# SCHE.net
KiCad netlist of a schematic drawn in Altium Designer
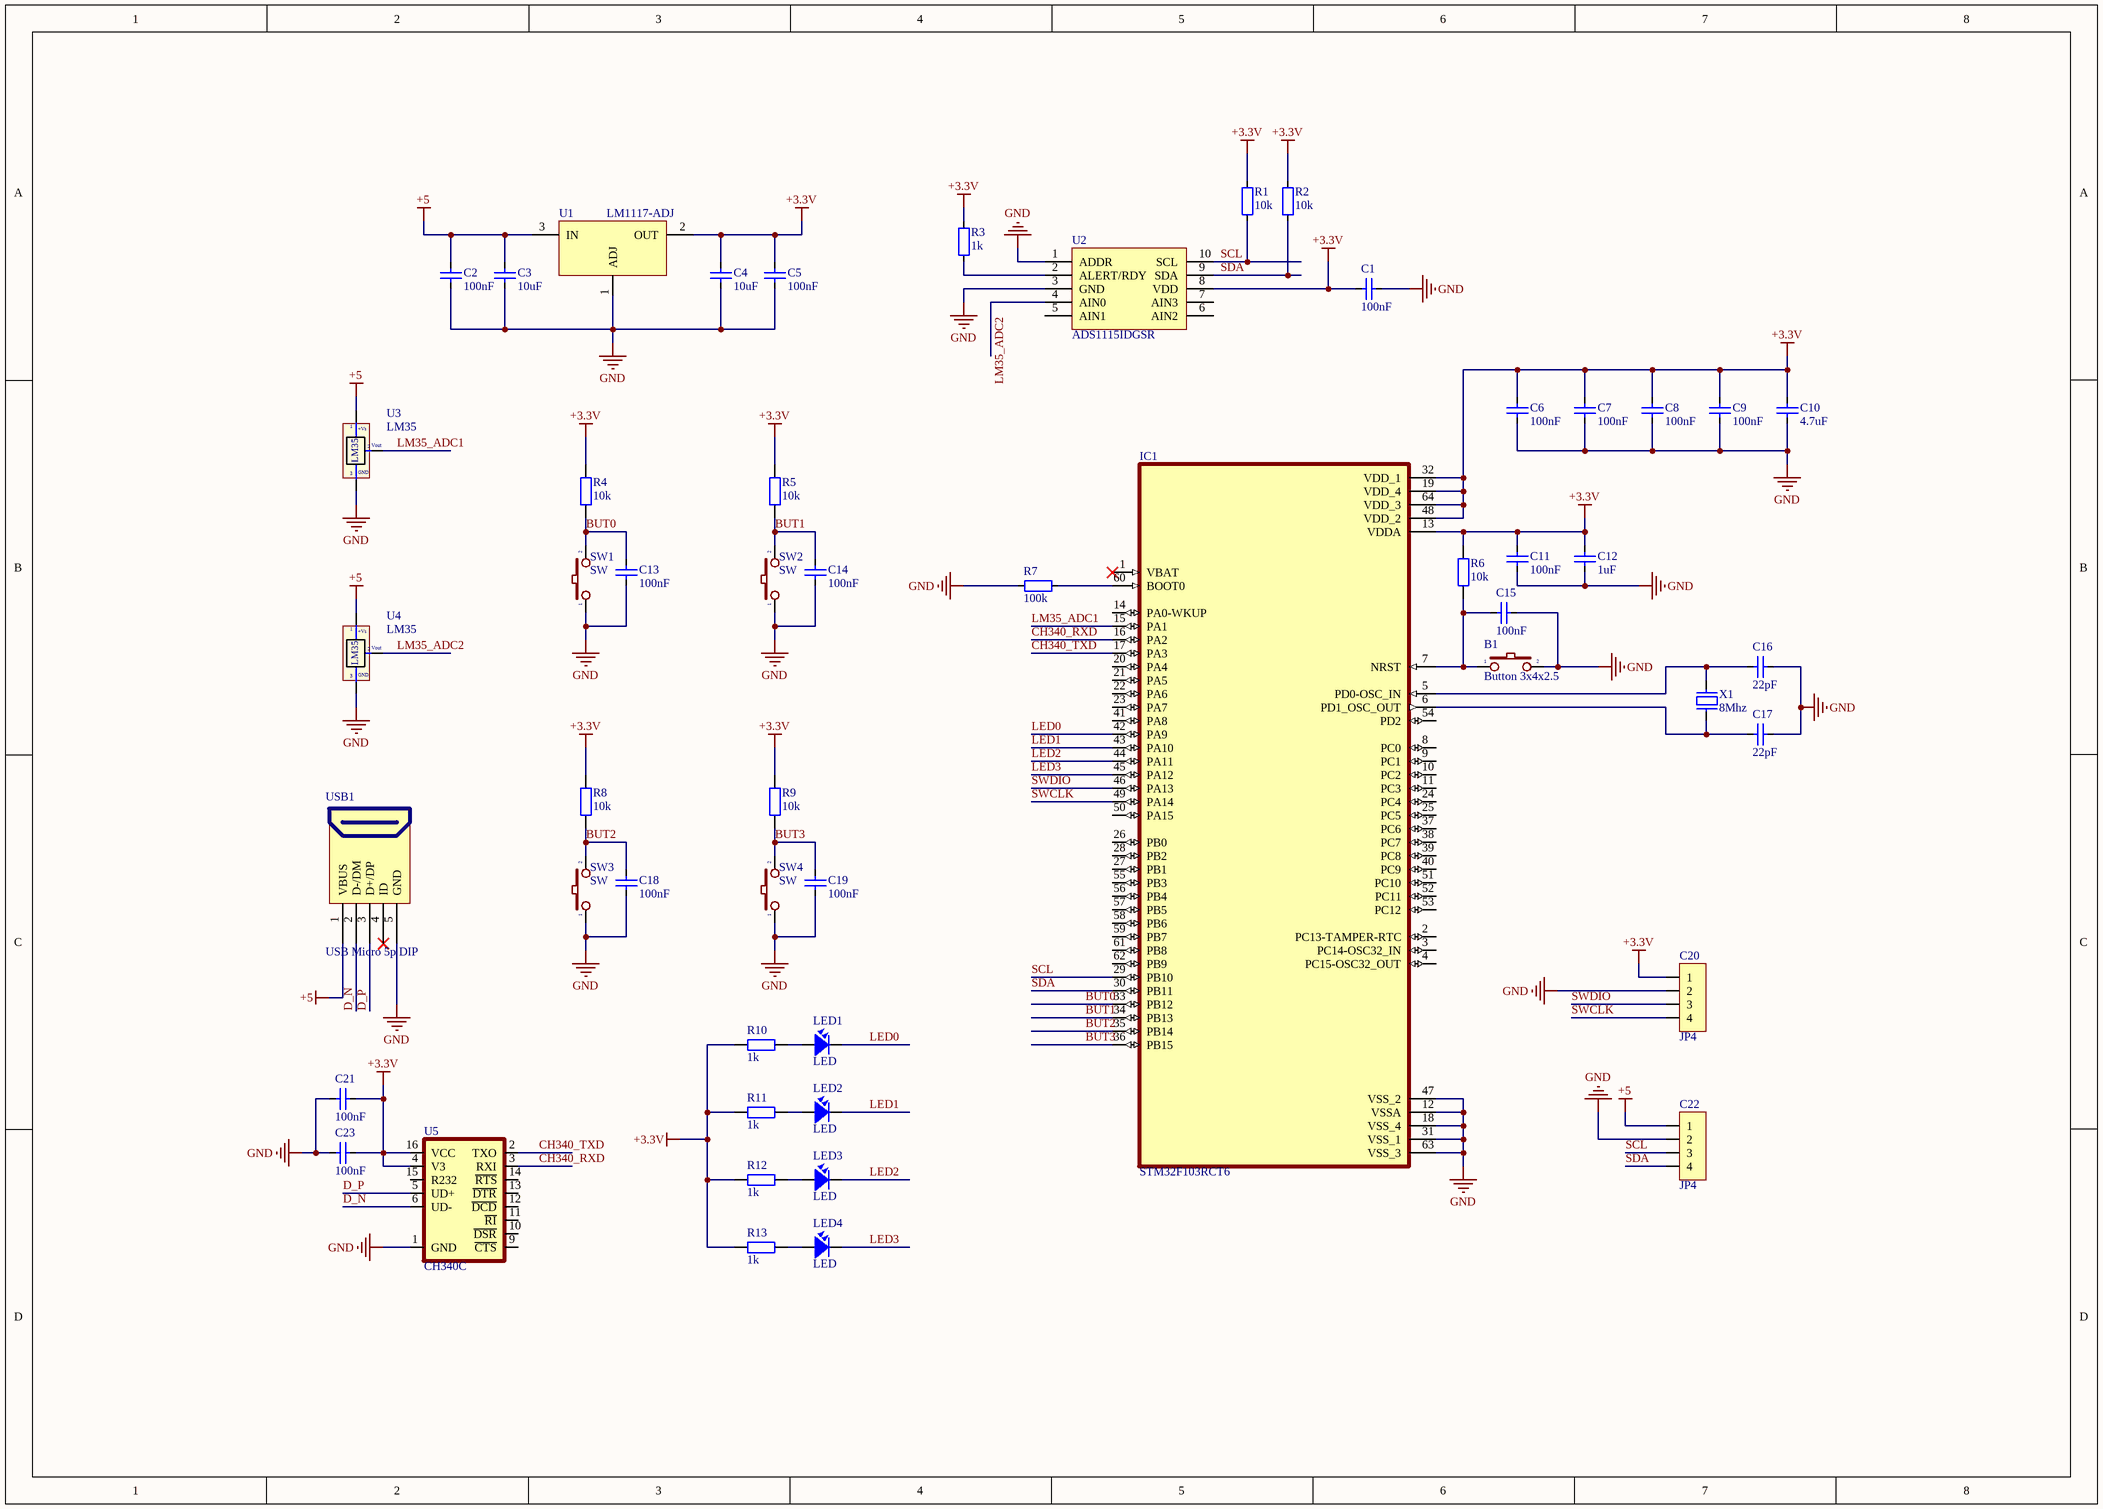
[diagram p0: SCHE.SchDoc]

(export (version "E")
  (design (tool "Eeschema 10.0.6"))
  (components
    (comp (ref "B1")
      (value "Button 3x4x2.5")
      (footprint "Button 3x4x2.5")
      (libsource (lib "My Library") (part "Button 3x4x2.5"))
    )
    (comp (ref "C1")
      (value "100nF")
      (footprint "CAP_0805")
      (description "Capacitor")
      (fields (field (name "PUBLISHER") "Altium Limited"))
      (libsource (lib "My Library") (part "CapSMD"))
    )
    (comp (ref "C2")
      (value "100nF")
      (footprint "CAP_0805")
      (description "Capacitor")
      (fields (field (name "PUBLISHER") "Altium Limited"))
      (libsource (lib "My Library") (part "CapSMD"))
    )
    (comp (ref "C3")
      (value "10uF")
      (footprint "CAP_0805")
      (description "Capacitor")
      (fields (field (name "PUBLISHER") "Altium Limited"))
      (libsource (lib "My Library") (part "CapSMD"))
    )
    (comp (ref "C4")
      (value "10uF")
      (footprint "CAP_0805")
      (description "Capacitor")
      (fields (field (name "PUBLISHER") "Altium Limited"))
      (libsource (lib "My Library") (part "CapSMD"))
    )
    (comp (ref "C5")
      (value "100nF")
      (footprint "CAP_0805")
      (description "Capacitor")
      (fields (field (name "PUBLISHER") "Altium Limited"))
      (libsource (lib "My Library") (part "CapSMD"))
    )
    (comp (ref "C6")
      (value "100nF")
      (footprint "CAP_0805")
      (description "Capacitor")
      (fields (field (name "PUBLISHER") "Altium Limited"))
      (libsource (lib "My Library") (part "CapSMD"))
    )
    (comp (ref "C7")
      (value "100nF")
      (footprint "CAP_0805")
      (description "Capacitor")
      (fields (field (name "PUBLISHER") "Altium Limited"))
      (libsource (lib "My Library") (part "CapSMD"))
    )
    (comp (ref "C8")
      (value "100nF")
      (footprint "CAP_0805")
      (description "Capacitor")
      (fields (field (name "PUBLISHER") "Altium Limited"))
      (libsource (lib "My Library") (part "CapSMD"))
    )
    (comp (ref "C9")
      (value "100nF")
      (footprint "CAP_0805")
      (description "Capacitor")
      (fields (field (name "PUBLISHER") "Altium Limited"))
      (libsource (lib "My Library") (part "CapSMD"))
    )
    (comp (ref "C10")
      (value "4.7uF")
      (footprint "CAP_0805")
      (description "Capacitor")
      (fields (field (name "PUBLISHER") "Altium Limited"))
      (libsource (lib "My Library") (part "CapSMD"))
    )
    (comp (ref "C11")
      (value "100nF")
      (footprint "CAP_0805")
      (description "Capacitor")
      (fields (field (name "PUBLISHER") "Altium Limited"))
      (libsource (lib "My Library") (part "CapSMD"))
    )
    (comp (ref "C12")
      (value "1uF")
      (footprint "CAP_0805")
      (description "Capacitor")
      (fields (field (name "PUBLISHER") "Altium Limited"))
      (libsource (lib "My Library") (part "CapSMD"))
    )
    (comp (ref "C13")
      (value "100nF")
      (footprint "CAP_0805")
      (description "Capacitor")
      (fields (field (name "PUBLISHER") "Altium Limited"))
      (libsource (lib "My Library") (part "CapSMD"))
    )
    (comp (ref "C14")
      (value "100nF")
      (footprint "CAP_0805")
      (description "Capacitor")
      (fields (field (name "PUBLISHER") "Altium Limited"))
      (libsource (lib "My Library") (part "CapSMD"))
    )
    (comp (ref "C15")
      (value "100nF")
      (footprint "CAP_0805")
      (description "Capacitor")
      (fields (field (name "PUBLISHER") "Altium Limited"))
      (libsource (lib "My Library") (part "CapSMD"))
    )
    (comp (ref "C16")
      (value "22pF")
      (footprint "CAP_0805")
      (description "Capacitor")
      (fields (field (name "PUBLISHER") "Altium Limited"))
      (libsource (lib "My Library") (part "CapSMD"))
    )
    (comp (ref "C17")
      (value "22pF")
      (footprint "CAP_0805")
      (description "Capacitor")
      (fields (field (name "PUBLISHER") "Altium Limited"))
      (libsource (lib "My Library") (part "CapSMD"))
    )
    (comp (ref "C18")
      (value "100nF")
      (footprint "CAP_0805")
      (description "Capacitor")
      (fields (field (name "PUBLISHER") "Altium Limited"))
      (libsource (lib "My Library") (part "CapSMD"))
    )
    (comp (ref "C19")
      (value "100nF")
      (footprint "CAP_0805")
      (description "Capacitor")
      (fields (field (name "PUBLISHER") "Altium Limited"))
      (libsource (lib "My Library") (part "CapSMD"))
    )
    (comp (ref "C20")
      (value "JP4")
      (footprint "JP4-C1T")
      (description "WR-PHD 2.54 mm Angled Socket Header")
      (fields
        (field (name "MANUFACTURER") "Würth Elektronik eiSos GmbH")
        (field (name "PARTNO") "613004143121")
        (field (name "CREATED BY") "Karrer Zheng")
      )
      (libsource (lib "My Library") (part "JP4"))
    )
    (comp (ref "C21")
      (value "100nF")
      (footprint "CAP_0805")
      (description "Capacitor")
      (fields (field (name "PUBLISHER") "Altium Limited"))
      (libsource (lib "My Library") (part "CapSMD"))
    )
    (comp (ref "C22")
      (value "JP4")
      (footprint "JP4-C1T")
      (description "WR-PHD 2.54 mm Angled Socket Header")
      (fields
        (field (name "MANUFACTURER") "Würth Elektronik eiSos GmbH")
        (field (name "PARTNO") "613004143121")
        (field (name "CREATED BY") "Karrer Zheng")
      )
      (libsource (lib "My Library") (part "JP4"))
    )
    (comp (ref "C23")
      (value "100nF")
      (footprint "CAP_0805")
      (description "Capacitor")
      (fields (field (name "PUBLISHER") "Altium Limited"))
      (libsource (lib "My Library") (part "CapSMD"))
    )
    (comp (ref "IC1")
      (value "STM32F103RCT6")
      (footprint "STM32F103RCT6")
      (libsource (lib "My Library") (part "STM32F103RCT6"))
    )
    (comp (ref "LED1")
      (value "LED")
      (footprint "LED-0805-Blue")
      (description "LED Single colour Green and Red")
      (libsource (lib "My Library") (part "LED"))
    )
    (comp (ref "LED2")
      (value "LED")
      (footprint "LED-0805-Green")
      (description "LED Single colour Green and Red")
      (libsource (lib "My Library") (part "LED"))
    )
    (comp (ref "LED3")
      (value "LED")
      (footprint "LED-0805-Orange")
      (description "LED Single colour Green and Red")
      (libsource (lib "My Library") (part "LED"))
    )
    (comp (ref "LED4")
      (value "LED")
      (footprint "LED-0805-Red")
      (description "LED Single colour Green and Red")
      (libsource (lib "My Library") (part "LED"))
    )
    (comp (ref "R1")
      (value "10k")
      (footprint "RES-SMD-0805")
      (description "Resistor")
      (fields
        (field (name "MANUFACTURER") "Generic Components")
        (field (name "PUBLISHER") "Altium Hobart Technology Centre")
      )
      (libsource (lib "") (part "Resistor - SMD_1"))
    )
    (comp (ref "R2")
      (value "10k")
      (footprint "RES-SMD-0805")
      (description "Resistor")
      (fields
        (field (name "MANUFACTURER") "Generic Components")
        (field (name "PUBLISHER") "Altium Hobart Technology Centre")
      )
      (libsource (lib "") (part "Resistor - SMD_1"))
    )
    (comp (ref "R3")
      (value "1k")
      (footprint "RES-SMD-0805")
      (description "Resistor")
      (fields
        (field (name "MANUFACTURER") "Generic Components")
        (field (name "PUBLISHER") "Altium Hobart Technology Centre")
      )
      (libsource (lib "") (part "Resistor - SMD_1"))
    )
    (comp (ref "R4")
      (value "10k")
      (footprint "RES-SMD-0805")
      (description "Resistor SMD")
      (fields
        (field (name "MANUFACTURER") "Generic Components")
        (field (name "PUBLISHER") "Altium Hobart Technology Centre")
      )
      (libsource (lib "My Library") (part "Resistor - SMD"))
    )
    (comp (ref "R5")
      (value "10k")
      (footprint "RES-SMD-0805")
      (description "Resistor SMD")
      (fields
        (field (name "MANUFACTURER") "Generic Components")
        (field (name "PUBLISHER") "Altium Hobart Technology Centre")
      )
      (libsource (lib "My Library") (part "Resistor - SMD"))
    )
    (comp (ref "R6")
      (value "10k")
      (footprint "RES-SMD-0805")
      (description "Resistor SMD")
      (fields
        (field (name "MANUFACTURER") "Generic Components")
        (field (name "PUBLISHER") "Altium Hobart Technology Centre")
      )
      (libsource (lib "My Library") (part "Resistor - SMD"))
    )
    (comp (ref "R7")
      (value "100k")
      (footprint "RES-SMD-0805")
      (description "Resistor")
      (fields
        (field (name "MANUFACTURER") "Generic Components")
        (field (name "PUBLISHER") "Altium Hobart Technology Centre")
      )
      (libsource (lib "") (part "Resistor - SMD_1"))
    )
    (comp (ref "R8")
      (value "10k")
      (footprint "RES-SMD-0805")
      (description "Resistor SMD")
      (fields
        (field (name "MANUFACTURER") "Generic Components")
        (field (name "PUBLISHER") "Altium Hobart Technology Centre")
      )
      (libsource (lib "My Library") (part "Resistor - SMD"))
    )
    (comp (ref "R9")
      (value "10k")
      (footprint "RES-SMD-0805")
      (description "Resistor SMD")
      (fields
        (field (name "MANUFACTURER") "Generic Components")
        (field (name "PUBLISHER") "Altium Hobart Technology Centre")
      )
      (libsource (lib "My Library") (part "Resistor - SMD"))
    )
    (comp (ref "R10")
      (value "1k")
      (footprint "RES-SMD-0805")
      (description "Resistor SMD")
      (fields
        (field (name "MANUFACTURER") "Generic Components")
        (field (name "PUBLISHER") "Altium Hobart Technology Centre")
      )
      (libsource (lib "My Library") (part "Resistor - SMD"))
    )
    (comp (ref "R11")
      (value "1k")
      (footprint "RES-SMD-0805")
      (description "Resistor SMD")
      (fields
        (field (name "MANUFACTURER") "Generic Components")
        (field (name "PUBLISHER") "Altium Hobart Technology Centre")
      )
      (libsource (lib "My Library") (part "Resistor - SMD"))
    )
    (comp (ref "R12")
      (value "1k")
      (footprint "RES-SMD-0805")
      (description "Resistor SMD")
      (fields
        (field (name "MANUFACTURER") "Generic Components")
        (field (name "PUBLISHER") "Altium Hobart Technology Centre")
      )
      (libsource (lib "My Library") (part "Resistor - SMD"))
    )
    (comp (ref "R13")
      (value "1k")
      (footprint "RES-SMD-0805")
      (description "Resistor SMD")
      (fields
        (field (name "MANUFACTURER") "Generic Components")
        (field (name "PUBLISHER") "Altium Hobart Technology Centre")
      )
      (libsource (lib "My Library") (part "Resistor - SMD"))
    )
    (comp (ref "SW1")
      (value "SW")
      (footprint "SW2")
      (description "Switch button 2 pin")
      (libsource (lib "My Library") (part "SW2"))
    )
    (comp (ref "SW2")
      (value "SW")
      (footprint "SW2")
      (description "Switch button 2 pin")
      (libsource (lib "My Library") (part "SW2"))
    )
    (comp (ref "SW3")
      (value "SW")
      (footprint "SW2")
      (description "Switch button 2 pin")
      (libsource (lib "My Library") (part "SW2"))
    )
    (comp (ref "SW4")
      (value "SW")
      (footprint "SW2")
      (description "Switch button 2 pin")
      (libsource (lib "My Library") (part "SW2"))
    )
    (comp (ref "U1")
      (value "LM1117-ADJ")
      (footprint "LM1117-SOP")
      (description "800mA Low-Dropout Linear Regulator")
      (fields (field (name "CREATOR") "Nguyen Ba Bien"))
      (libsource (lib "My Library") (part "LM1117-ADJ"))
    )
    (comp (ref "U2")
      (value "ADS1115IDGSR")
      (footprint "VSOP-10_19.6_230_57X12_SMD")
      (description "Analog to Digital Converters - ADC 16B ADC w/ Int MUX PGA Comp Osc & Ref")
      (fields (field (name "MANUFACTURER") "Texas Instruments"))
      (libsource (lib "Altium_Lib_by_KhueNguyenCreator") (part "IC_ADS1115IDGSR"))
    )
    (comp (ref "U3")
      (value "LM35")
      (footprint "QTO-92")
      (description "Teminal")
      (libsource (lib "My Library") (part "LM35"))
    )
    (comp (ref "U4")
      (value "LM35")
      (footprint "QTO-92")
      (description "Teminal")
      (libsource (lib "My Library") (part "LM35"))
    )
    (comp (ref "U5")
      (value "CH340C")
      (footprint "SO016")
      (description "USB to serial chip CH340")
      (fields (field (name "MF") "WCH"))
      (libsource (lib "My Library") (part "CH340C"))
    )
    (comp (ref "USB1")
      (value "USB Micro 5p DIP")
      (footprint "USB Micro 5p DIP")
      (description "USB Type B")
      (libsource (lib "Altium_Lib_by_KhueNguyenCreator") (part "USB Micro 5p DIP"))
    )
    (comp (ref "X1")
      (value "8Mhz")
      (footprint "XTAL 5032 SMD")
      (description "Crystal For all Crystal 2pin.")
      (libsource (lib "My Library") (part "XT2"))
    )
  )
  (nets
    (net (code "1") (name "+3.3V") (class "Default")
      (node (ref "C1") (pin "1") (pinfunction "1_1") (pintype "passive"))
      (node (ref "C10") (pin "2") (pinfunction "2_2") (pintype "passive"))
      (node (ref "C11") (pin "2") (pinfunction "2_2") (pintype "passive"))
      (node (ref "C12") (pin "2") (pinfunction "2_2") (pintype "passive"))
      (node (ref "C20") (pin "1") (pinfunction "1_1") (pintype "passive"))
      (node (ref "C21") (pin "2") (pinfunction "2_2") (pintype "passive"))
      (node (ref "C23") (pin "2") (pinfunction "2_2") (pintype "passive"))
      (node (ref "C4") (pin "1") (pinfunction "1_1") (pintype "passive"))
      (node (ref "C5") (pin "1") (pinfunction "1_1") (pintype "passive"))
      (node (ref "C6") (pin "2") (pinfunction "2_2") (pintype "passive"))
      (node (ref "C7") (pin "2") (pinfunction "2_2") (pintype "passive"))
      (node (ref "C8") (pin "2") (pinfunction "2_2") (pintype "passive"))
      (node (ref "C9") (pin "2") (pinfunction "2_2") (pintype "passive"))
      (node (ref "IC1") (pin "13") (pinfunction "VDDA_13") (pintype "power_in"))
      (node (ref "IC1") (pin "19") (pinfunction "VDD_4_19") (pintype "power_in"))
      (node (ref "IC1") (pin "32") (pinfunction "VDD_1_32") (pintype "power_in"))
      (node (ref "IC1") (pin "48") (pinfunction "VDD_2_48") (pintype "power_in"))
      (node (ref "IC1") (pin "64") (pinfunction "VDD_3_64") (pintype "power_in"))
      (node (ref "R1") (pin "1") (pinfunction "1_1") (pintype "passive"))
      (node (ref "R10") (pin "1") (pinfunction "1_1") (pintype "passive"))
      (node (ref "R11") (pin "1") (pinfunction "1_1") (pintype "passive"))
      (node (ref "R12") (pin "1") (pinfunction "1_1") (pintype "passive"))
      (node (ref "R13") (pin "1") (pinfunction "1_1") (pintype "passive"))
      (node (ref "R2") (pin "1") (pinfunction "1_1") (pintype "passive"))
      (node (ref "R3") (pin "1") (pinfunction "1_1") (pintype "passive"))
      (node (ref "R4") (pin "1") (pinfunction "1_1") (pintype "passive"))
      (node (ref "R5") (pin "1") (pinfunction "1_1") (pintype "passive"))
      (node (ref "R6") (pin "2") (pinfunction "2_2") (pintype "passive"))
      (node (ref "R8") (pin "1") (pinfunction "1_1") (pintype "passive"))
      (node (ref "R9") (pin "1") (pinfunction "1_1") (pintype "passive"))
      (node (ref "U1") (pin "2") (pinfunction "OUT_2") (pintype "passive"))
      (node (ref "U2") (pin "8") (pinfunction "VDD_8") (pintype "passive"))
      (node (ref "U5") (pin "16") (pinfunction "VCC_16") (pintype "bidirectional"))
      (node (ref "U5") (pin "4") (pinfunction "V3_4") (pintype "bidirectional"))
    )
    (net (code "2") (name "+5") (class "Default")
      (node (ref "C2") (pin "1") (pinfunction "1_1") (pintype "passive"))
      (node (ref "C22") (pin "1") (pinfunction "1_1") (pintype "passive"))
      (node (ref "C3") (pin "1") (pinfunction "1_1") (pintype "passive"))
      (node (ref "U1") (pin "3") (pinfunction "IN_3") (pintype "passive"))
      (node (ref "U3") (pin "1") (pinfunction "+Vs_1") (pintype "passive"))
      (node (ref "U4") (pin "1") (pinfunction "+Vs_1") (pintype "passive"))
      (node (ref "USB1") (pin "1") (pinfunction "VBUS_1") (pintype "passive"))
    )
    (net (code "3") (name "/BUT0") (class "Default")
      (node (ref "C13") (pin "2") (pinfunction "2_2") (pintype "passive"))
      (node (ref "IC1") (pin "33") (pinfunction "PB12_33") (pintype "bidirectional"))
      (node (ref "R4") (pin "2") (pinfunction "2_2") (pintype "passive"))
      (node (ref "SW1") (pin "2") (pinfunction "2_2") (pintype "passive"))
    )
    (net (code "4") (name "/BUT1") (class "Default")
      (node (ref "C14") (pin "2") (pinfunction "2_2") (pintype "passive"))
      (node (ref "IC1") (pin "34") (pinfunction "PB13_34") (pintype "bidirectional"))
      (node (ref "R5") (pin "2") (pinfunction "2_2") (pintype "passive"))
      (node (ref "SW2") (pin "2") (pinfunction "2_2") (pintype "passive"))
    )
    (net (code "5") (name "/BUT2") (class "Default")
      (node (ref "C18") (pin "2") (pinfunction "2_2") (pintype "passive"))
      (node (ref "IC1") (pin "35") (pinfunction "PB14_35") (pintype "bidirectional"))
      (node (ref "R8") (pin "2") (pinfunction "2_2") (pintype "passive"))
      (node (ref "SW3") (pin "2") (pinfunction "2_2") (pintype "passive"))
    )
    (net (code "6") (name "/BUT3") (class "Default")
      (node (ref "C19") (pin "2") (pinfunction "2_2") (pintype "passive"))
      (node (ref "IC1") (pin "36") (pinfunction "PB15_36") (pintype "bidirectional"))
      (node (ref "R9") (pin "2") (pinfunction "2_2") (pintype "passive"))
      (node (ref "SW4") (pin "2") (pinfunction "2_2") (pintype "passive"))
    )
    (net (code "7") (name "/CH340_RXD") (class "Default")
      (node (ref "IC1") (pin "16") (pinfunction "PA2_16") (pintype "bidirectional"))
      (node (ref "U5") (pin "3") (pinfunction "RXI_3") (pintype "bidirectional"))
    )
    (net (code "8") (name "/CH340_TXD") (class "Default")
      (node (ref "IC1") (pin "17") (pinfunction "PA3_17") (pintype "bidirectional"))
      (node (ref "U5") (pin "2") (pinfunction "TXO_2") (pintype "bidirectional"))
    )
    (net (code "9") (name "/D_N") (class "Default")
      (node (ref "U5") (pin "6") (pinfunction "UD-_6") (pintype "bidirectional"))
      (node (ref "USB1") (pin "2") (pinfunction "D-/DM_2") (pintype "passive"))
    )
    (net (code "10") (name "/D_P") (class "Default")
      (node (ref "U5") (pin "5") (pinfunction "UD+_5") (pintype "bidirectional"))
      (node (ref "USB1") (pin "3") (pinfunction "D+/DP_3") (pintype "passive"))
    )
    (net (code "11") (name "/LED0") (class "Default")
      (node (ref "IC1") (pin "42") (pinfunction "PA9_42") (pintype "bidirectional"))
      (node (ref "LED1") (pin "2") (pinfunction "2_2") (pintype "passive"))
    )
    (net (code "12") (name "/LED1") (class "Default")
      (node (ref "IC1") (pin "43") (pinfunction "PA10_43") (pintype "bidirectional"))
      (node (ref "LED2") (pin "2") (pinfunction "2_2") (pintype "passive"))
    )
    (net (code "13") (name "/LED2") (class "Default")
      (node (ref "IC1") (pin "44") (pinfunction "PA11_44") (pintype "bidirectional"))
      (node (ref "LED3") (pin "2") (pinfunction "2_2") (pintype "passive"))
    )
    (net (code "14") (name "/LED3") (class "Default")
      (node (ref "IC1") (pin "45") (pinfunction "PA12_45") (pintype "bidirectional"))
      (node (ref "LED4") (pin "2") (pinfunction "2_2") (pintype "passive"))
    )
    (net (code "15") (name "/LM35_ADC1") (class "Default")
      (node (ref "IC1") (pin "15") (pinfunction "PA1_15") (pintype "bidirectional"))
      (node (ref "U3") (pin "2") (pinfunction "Vout_2") (pintype "passive"))
    )
    (net (code "16") (name "/LM35_ADC2") (class "Default")
      (node (ref "U2") (pin "4") (pinfunction "AIN0_4") (pintype "passive"))
      (node (ref "U4") (pin "2") (pinfunction "Vout_2") (pintype "passive"))
    )
    (net (code "17") (name "/SCL") (class "Default")
      (node (ref "C22") (pin "3") (pinfunction "3_3") (pintype "passive"))
      (node (ref "IC1") (pin "29") (pinfunction "PB10_29") (pintype "bidirectional"))
      (node (ref "R1") (pin "2") (pinfunction "2_2") (pintype "passive"))
      (node (ref "U2") (pin "10") (pinfunction "SCL_10") (pintype "passive"))
    )
    (net (code "18") (name "/SDA") (class "Default")
      (node (ref "C22") (pin "4") (pinfunction "4_4") (pintype "passive"))
      (node (ref "IC1") (pin "30") (pinfunction "PB11_30") (pintype "bidirectional"))
      (node (ref "R2") (pin "2") (pinfunction "2_2") (pintype "passive"))
      (node (ref "U2") (pin "9") (pinfunction "SDA_9") (pintype "passive"))
    )
    (net (code "19") (name "/SWCLK") (class "Default")
      (node (ref "C20") (pin "4") (pinfunction "4_4") (pintype "passive"))
      (node (ref "IC1") (pin "49") (pinfunction "PA14_49") (pintype "bidirectional"))
    )
    (net (code "20") (name "/SWDIO") (class "Default")
      (node (ref "C20") (pin "3") (pinfunction "3_3") (pintype "passive"))
      (node (ref "IC1") (pin "46") (pinfunction "PA13_46") (pintype "bidirectional"))
    )
    (net (code "21") (name "GND") (class "Default")
      (node (ref "B1") (pin "2") (pinfunction "2_2") (pintype "passive"))
      (node (ref "C1") (pin "2") (pinfunction "2_2") (pintype "passive"))
      (node (ref "C10") (pin "1") (pinfunction "1_1") (pintype "passive"))
      (node (ref "C11") (pin "1") (pinfunction "1_1") (pintype "passive"))
      (node (ref "C12") (pin "1") (pinfunction "1_1") (pintype "passive"))
      (node (ref "C13") (pin "1") (pinfunction "1_1") (pintype "passive"))
      (node (ref "C14") (pin "1") (pinfunction "1_1") (pintype "passive"))
      (node (ref "C15") (pin "1") (pinfunction "1_1") (pintype "passive"))
      (node (ref "C16") (pin "1") (pinfunction "1_1") (pintype "passive"))
      (node (ref "C17") (pin "1") (pinfunction "1_1") (pintype "passive"))
      (node (ref "C18") (pin "1") (pinfunction "1_1") (pintype "passive"))
      (node (ref "C19") (pin "1") (pinfunction "1_1") (pintype "passive"))
      (node (ref "C2") (pin "2") (pinfunction "2_2") (pintype "passive"))
      (node (ref "C20") (pin "2") (pinfunction "2_2") (pintype "passive"))
      (node (ref "C21") (pin "1") (pinfunction "1_1") (pintype "passive"))
      (node (ref "C22") (pin "2") (pinfunction "2_2") (pintype "passive"))
      (node (ref "C23") (pin "1") (pinfunction "1_1") (pintype "passive"))
      (node (ref "C3") (pin "2") (pinfunction "2_2") (pintype "passive"))
      (node (ref "C4") (pin "2") (pinfunction "2_2") (pintype "passive"))
      (node (ref "C5") (pin "2") (pinfunction "2_2") (pintype "passive"))
      (node (ref "C6") (pin "1") (pinfunction "1_1") (pintype "passive"))
      (node (ref "C7") (pin "1") (pinfunction "1_1") (pintype "passive"))
      (node (ref "C8") (pin "1") (pinfunction "1_1") (pintype "passive"))
      (node (ref "C9") (pin "1") (pinfunction "1_1") (pintype "passive"))
      (node (ref "IC1") (pin "12") (pinfunction "VSSA_12") (pintype "power_in"))
      (node (ref "IC1") (pin "18") (pinfunction "VSS_4_18") (pintype "power_in"))
      (node (ref "IC1") (pin "31") (pinfunction "VSS_1_31") (pintype "power_in"))
      (node (ref "IC1") (pin "47") (pinfunction "VSS_2_47") (pintype "power_in"))
      (node (ref "IC1") (pin "63") (pinfunction "VSS_3_63") (pintype "power_in"))
      (node (ref "R7") (pin "1") (pinfunction "1_1") (pintype "passive"))
      (node (ref "SW1") (pin "1") (pinfunction "1_1") (pintype "passive"))
      (node (ref "SW2") (pin "1") (pinfunction "1_1") (pintype "passive"))
      (node (ref "SW3") (pin "1") (pinfunction "1_1") (pintype "passive"))
      (node (ref "SW4") (pin "1") (pinfunction "1_1") (pintype "passive"))
      (node (ref "U1") (pin "1") (pinfunction "ADJ_1") (pintype "passive"))
      (node (ref "U2") (pin "1") (pinfunction "ADDR_1") (pintype "passive"))
      (node (ref "U2") (pin "3") (pinfunction "GND_3") (pintype "passive"))
      (node (ref "U3") (pin "3") (pinfunction "-_3") (pintype "passive"))
      (node (ref "U4") (pin "3") (pinfunction "-_3") (pintype "passive"))
      (node (ref "U5") (pin "1") (pinfunction "GND_1") (pintype "bidirectional"))
      (node (ref "USB1") (pin "5") (pinfunction "GND_5") (pintype "passive"))
    )
    (net (code "22") (name "Net-(IC1-BOOT0)") (class "Default")
      (node (ref "IC1") (pin "60") (pinfunction "BOOT0_60") (pintype "input"))
      (node (ref "R7") (pin "2") (pinfunction "2_2") (pintype "passive"))
    )
    (net (code "23") (name "Net-(IC1-NRST)") (class "Default")
      (node (ref "B1") (pin "1") (pinfunction "1_1") (pintype "passive"))
      (node (ref "C15") (pin "2") (pinfunction "2_2") (pintype "passive"))
      (node (ref "IC1") (pin "7") (pinfunction "NRST_7") (pintype "input"))
      (node (ref "R6") (pin "1") (pinfunction "1_1") (pintype "passive"))
    )
    (net (code "24") (name "Net-(IC1-PD0-OSC_IN)") (class "Default")
      (node (ref "C16") (pin "2") (pinfunction "2_2") (pintype "passive"))
      (node (ref "IC1") (pin "5") (pinfunction "PD0-OSC_IN_5") (pintype "input"))
      (node (ref "X1") (pin "2") (pinfunction "2_2") (pintype "passive"))
    )
    (net (code "25") (name "Net-(IC1-PD1_OSC_OUT)") (class "Default")
      (node (ref "C17") (pin "2") (pinfunction "2_2") (pintype "passive"))
      (node (ref "IC1") (pin "6") (pinfunction "PD1_OSC_OUT_6") (pintype "output"))
      (node (ref "X1") (pin "1") (pinfunction "1_1") (pintype "passive"))
    )
    (net (code "26") (name "Net-(LED1-Pad1)") (class "Default")
      (node (ref "LED1") (pin "1") (pinfunction "1_1") (pintype "passive"))
      (node (ref "R10") (pin "2") (pinfunction "2_2") (pintype "passive"))
    )
    (net (code "27") (name "Net-(LED2-Pad1)") (class "Default")
      (node (ref "LED2") (pin "1") (pinfunction "1_1") (pintype "passive"))
      (node (ref "R11") (pin "2") (pinfunction "2_2") (pintype "passive"))
    )
    (net (code "28") (name "Net-(LED3-Pad1)") (class "Default")
      (node (ref "LED3") (pin "1") (pinfunction "1_1") (pintype "passive"))
      (node (ref "R12") (pin "2") (pinfunction "2_2") (pintype "passive"))
    )
    (net (code "29") (name "Net-(LED4-Pad1)") (class "Default")
      (node (ref "LED4") (pin "1") (pinfunction "1_1") (pintype "passive"))
      (node (ref "R13") (pin "2") (pinfunction "2_2") (pintype "passive"))
    )
    (net (code "30") (name "Net-(U2-ALERT{slash}RDY)") (class "Default")
      (node (ref "R3") (pin "2") (pinfunction "2_2") (pintype "passive"))
      (node (ref "U2") (pin "2") (pinfunction "ALERT/RDY_2") (pintype "passive"))
    )
    (net (code "31") (name "unconnected-(IC1-PA0-WKUP-Pad14)") (class "Default")
      (node (ref "IC1") (pin "14") (pinfunction "PA0-WKUP_14") (pintype "bidirectional"))
    )
    (net (code "32") (name "unconnected-(IC1-PA4-Pad20)") (class "Default")
      (node (ref "IC1") (pin "20") (pinfunction "PA4_20") (pintype "bidirectional"))
    )
    (net (code "33") (name "unconnected-(IC1-PA5-Pad21)") (class "Default")
      (node (ref "IC1") (pin "21") (pinfunction "PA5_21") (pintype "bidirectional"))
    )
    (net (code "34") (name "unconnected-(IC1-PA6-Pad22)") (class "Default")
      (node (ref "IC1") (pin "22") (pinfunction "PA6_22") (pintype "bidirectional"))
    )
    (net (code "35") (name "unconnected-(IC1-PA7-Pad23)") (class "Default")
      (node (ref "IC1") (pin "23") (pinfunction "PA7_23") (pintype "bidirectional"))
    )
    (net (code "36") (name "unconnected-(IC1-PA8-Pad41)") (class "Default")
      (node (ref "IC1") (pin "41") (pinfunction "PA8_41") (pintype "bidirectional"))
    )
    (net (code "37") (name "unconnected-(IC1-PA15-Pad50)") (class "Default")
      (node (ref "IC1") (pin "50") (pinfunction "PA15_50") (pintype "bidirectional"))
    )
    (net (code "38") (name "unconnected-(IC1-PB0-Pad26)") (class "Default")
      (node (ref "IC1") (pin "26") (pinfunction "PB0_26") (pintype "bidirectional"))
    )
    (net (code "39") (name "unconnected-(IC1-PB1-Pad27)") (class "Default")
      (node (ref "IC1") (pin "27") (pinfunction "PB1_27") (pintype "bidirectional"))
    )
    (net (code "40") (name "unconnected-(IC1-PB2-Pad28)") (class "Default")
      (node (ref "IC1") (pin "28") (pinfunction "PB2_28") (pintype "bidirectional"))
    )
    (net (code "41") (name "unconnected-(IC1-PB3-Pad55)") (class "Default")
      (node (ref "IC1") (pin "55") (pinfunction "PB3_55") (pintype "bidirectional"))
    )
    (net (code "42") (name "unconnected-(IC1-PB4-Pad56)") (class "Default")
      (node (ref "IC1") (pin "56") (pinfunction "PB4_56") (pintype "bidirectional"))
    )
    (net (code "43") (name "unconnected-(IC1-PB5-Pad57)") (class "Default")
      (node (ref "IC1") (pin "57") (pinfunction "PB5_57") (pintype "bidirectional"))
    )
    (net (code "44") (name "unconnected-(IC1-PB6-Pad58)") (class "Default")
      (node (ref "IC1") (pin "58") (pinfunction "PB6_58") (pintype "bidirectional"))
    )
    (net (code "45") (name "unconnected-(IC1-PB7-Pad59)") (class "Default")
      (node (ref "IC1") (pin "59") (pinfunction "PB7_59") (pintype "bidirectional"))
    )
    (net (code "46") (name "unconnected-(IC1-PB8-Pad61)") (class "Default")
      (node (ref "IC1") (pin "61") (pinfunction "PB8_61") (pintype "bidirectional"))
    )
    (net (code "47") (name "unconnected-(IC1-PB9-Pad62)") (class "Default")
      (node (ref "IC1") (pin "62") (pinfunction "PB9_62") (pintype "bidirectional"))
    )
    (net (code "48") (name "unconnected-(IC1-PC0-Pad8)") (class "Default")
      (node (ref "IC1") (pin "8") (pinfunction "PC0_8") (pintype "bidirectional"))
    )
    (net (code "49") (name "unconnected-(IC1-PC1-Pad9)") (class "Default")
      (node (ref "IC1") (pin "9") (pinfunction "PC1_9") (pintype "bidirectional"))
    )
    (net (code "50") (name "unconnected-(IC1-PC2-Pad10)") (class "Default")
      (node (ref "IC1") (pin "10") (pinfunction "PC2_10") (pintype "bidirectional"))
    )
    (net (code "51") (name "unconnected-(IC1-PC3-Pad11)") (class "Default")
      (node (ref "IC1") (pin "11") (pinfunction "PC3_11") (pintype "bidirectional"))
    )
    (net (code "52") (name "unconnected-(IC1-PC4-Pad24)") (class "Default")
      (node (ref "IC1") (pin "24") (pinfunction "PC4_24") (pintype "bidirectional"))
    )
    (net (code "53") (name "unconnected-(IC1-PC5-Pad25)") (class "Default")
      (node (ref "IC1") (pin "25") (pinfunction "PC5_25") (pintype "bidirectional"))
    )
    (net (code "54") (name "unconnected-(IC1-PC6-Pad37)") (class "Default")
      (node (ref "IC1") (pin "37") (pinfunction "PC6_37") (pintype "bidirectional"))
    )
    (net (code "55") (name "unconnected-(IC1-PC7-Pad38)") (class "Default")
      (node (ref "IC1") (pin "38") (pinfunction "PC7_38") (pintype "bidirectional"))
    )
    (net (code "56") (name "unconnected-(IC1-PC8-Pad39)") (class "Default")
      (node (ref "IC1") (pin "39") (pinfunction "PC8_39") (pintype "bidirectional"))
    )
    (net (code "57") (name "unconnected-(IC1-PC9-Pad40)") (class "Default")
      (node (ref "IC1") (pin "40") (pinfunction "PC9_40") (pintype "bidirectional"))
    )
    (net (code "58") (name "unconnected-(IC1-PC10-Pad51)") (class "Default")
      (node (ref "IC1") (pin "51") (pinfunction "PC10_51") (pintype "bidirectional"))
    )
    (net (code "59") (name "unconnected-(IC1-PC11-Pad52)") (class "Default")
      (node (ref "IC1") (pin "52") (pinfunction "PC11_52") (pintype "bidirectional"))
    )
    (net (code "60") (name "unconnected-(IC1-PC12-Pad53)") (class "Default")
      (node (ref "IC1") (pin "53") (pinfunction "PC12_53") (pintype "bidirectional"))
    )
    (net (code "61") (name "unconnected-(IC1-PC13-TAMPER-RTC-Pad2)") (class "Default")
      (node (ref "IC1") (pin "2") (pinfunction "PC13-TAMPER-RTC_2") (pintype "bidirectional"))
    )
    (net (code "62") (name "unconnected-(IC1-PC14-OSC32_IN-Pad3)") (class "Default")
      (node (ref "IC1") (pin "3") (pinfunction "PC14-OSC32_IN_3") (pintype "bidirectional"))
    )
    (net (code "63") (name "unconnected-(IC1-PC15-OSC32_OUT-Pad4)") (class "Default")
      (node (ref "IC1") (pin "4") (pinfunction "PC15-OSC32_OUT_4") (pintype "bidirectional"))
    )
    (net (code "64") (name "unconnected-(IC1-PD2-Pad54)") (class "Default")
      (node (ref "IC1") (pin "54") (pinfunction "PD2_54") (pintype "bidirectional"))
    )
    (net (code "65") (name "unconnected-(IC1-VBAT-Pad1)") (class "Default")
      (node (ref "IC1") (pin "1") (pinfunction "VBAT_1") (pintype "input+no_connect"))
    )
    (net (code "66") (name "unconnected-(U2-AIN1-Pad5)") (class "Default")
      (node (ref "U2") (pin "5") (pinfunction "AIN1_5") (pintype "passive"))
    )
    (net (code "67") (name "unconnected-(U2-AIN2-Pad6)") (class "Default")
      (node (ref "U2") (pin "6") (pinfunction "AIN2_6") (pintype "passive"))
    )
    (net (code "68") (name "unconnected-(U2-AIN3-Pad7)") (class "Default")
      (node (ref "U2") (pin "7") (pinfunction "AIN3_7") (pintype "passive"))
    )
    (net (code "69") (name "unconnected-(U5-R232-Pad15)") (class "Default")
      (node (ref "U5") (pin "15") (pinfunction "R232_15") (pintype "bidirectional"))
    )
    (net (code "70") (name "unconnected-(U5-~{CTS}-Pad9)") (class "Default")
      (node (ref "U5") (pin "9") (pinfunction "~{CTS}_9") (pintype "bidirectional"))
    )
    (net (code "71") (name "unconnected-(U5-~{DCD}-Pad12)") (class "Default")
      (node (ref "U5") (pin "12") (pinfunction "~{DCD}_12") (pintype "bidirectional"))
    )
    (net (code "72") (name "unconnected-(U5-~{DSR}-Pad10)") (class "Default")
      (node (ref "U5") (pin "10") (pinfunction "~{DSR}_10") (pintype "bidirectional"))
    )
    (net (code "73") (name "unconnected-(U5-~{DTR}-Pad13)") (class "Default")
      (node (ref "U5") (pin "13") (pinfunction "~{DTR}_13") (pintype "bidirectional"))
    )
    (net (code "74") (name "unconnected-(U5-~{RI}-Pad11)") (class "Default")
      (node (ref "U5") (pin "11") (pinfunction "~{RI}_11") (pintype "bidirectional"))
    )
    (net (code "75") (name "unconnected-(U5-~{RTS}-Pad14)") (class "Default")
      (node (ref "U5") (pin "14") (pinfunction "~{RTS}_14") (pintype "bidirectional"))
    )
    (net (code "76") (name "unconnected-(USB1-ID-Pad4)") (class "Default")
      (node (ref "USB1") (pin "4") (pinfunction "ID_4") (pintype "passive+no_connect"))
    )
  )
)
